# battery_monitor.net
KiCad netlist of a schematic drawn in Altium Designer
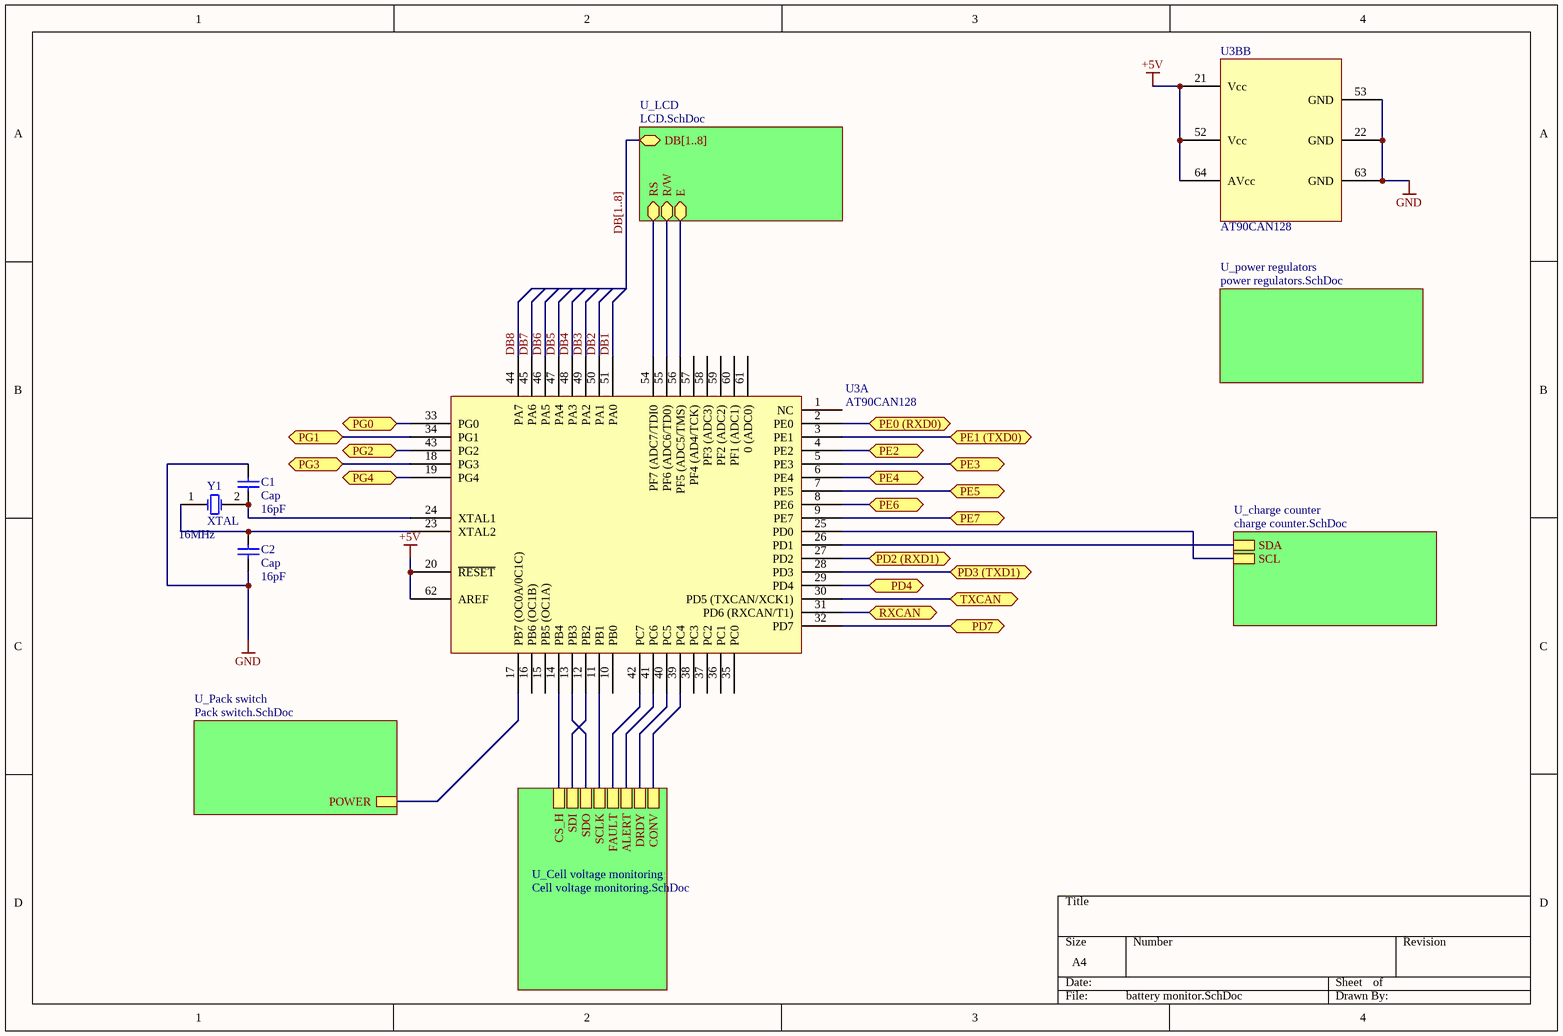
[diagram p0: battery monitor.SchDoc]

(export (version "E")
  (design (tool "Eeschema 10.0.6"))
  (components
    (comp (ref "C1")
      (value "Cap")
      (footprint "C0805")
      (description "Capacitor")
      (fields (field (name "ALTIUM_VALUE") "16pF") (field (name "PUBLISHER") "Altium Limited"))
      (libsource (lib "Miscellaneous Devices") (part "Cap"))
    )
    (comp (ref "C2")
      (value "Cap")
      (footprint "C0805")
      (description "Capacitor")
      (fields (field (name "ALTIUM_VALUE") "16pF") (field (name "PUBLISHER") "Altium Limited"))
      (libsource (lib "Miscellaneous Devices") (part "Cap"))
    )
    (comp (ref "U3")
      (value "AT90CAN128")
      (footprint "TQFP80P1600X1600X120-64N")
      (libsource (lib "") (part "AT90CAN128_1"))
    )
    (comp (ref "U3B")
      (value "AT90CAN128")
      (footprint "TQFP80P1600X1600X120-64N")
      (libsource (lib "AT90CAN128") (part "AT90CAN128"))
    )
    (comp (ref "Y1")
      (value "XTAL")
      (footprint "R38")
      (description "Crystal Oscillator")
      (fields (field (name "ALTIUM_VALUE") "16MHz") (field (name "PUBLISHER") "Altium Limited"))
      (libsource (lib "Miscellaneous Devices") (part "XTAL"))
    )
  )
  (nets
    (net (code "1") (name "+5V") (class "Default")
      (node (ref "U3") (pin "20") (pinfunction "~{RESET}_20") (pintype "passive"))
      (node (ref "U3") (pin "62") (pinfunction "AREF_62") (pintype "passive"))
      (node (ref "U3B") (pin "21") (pinfunction "Vcc_21") (pintype "passive"))
      (node (ref "U3B") (pin "52") (pinfunction "Vcc_52") (pintype "passive"))
      (node (ref "U3B") (pin "64") (pinfunction "AVcc_64") (pintype "passive"))
    )
    (net (code "2") (name "/ALERT") (class "Default")
      (node (ref "U3") (pin "41") (pinfunction "PC6_41") (pintype "passive"))
    )
    (net (code "3") (name "/CONV") (class "Default")
      (node (ref "U3") (pin "39") (pinfunction "PC4_39") (pintype "passive"))
    )
    (net (code "4") (name "/CS_H") (class "Default")
      (node (ref "U3") (pin "14") (pinfunction "PB4_14") (pintype "passive"))
    )
    (net (code "5") (name "/DB1") (class "Default")
      (node (ref "U3") (pin "51") (pinfunction "PA0_51") (pintype "passive"))
    )
    (net (code "6") (name "/DB2") (class "Default")
      (node (ref "U3") (pin "50") (pinfunction "PA1_50") (pintype "passive"))
    )
    (net (code "7") (name "/DB3") (class "Default")
      (node (ref "U3") (pin "49") (pinfunction "PA2_49") (pintype "passive"))
    )
    (net (code "8") (name "/DB4") (class "Default")
      (node (ref "U3") (pin "48") (pinfunction "PA3_48") (pintype "passive"))
    )
    (net (code "9") (name "/DB5") (class "Default")
      (node (ref "U3") (pin "47") (pinfunction "PA4_47") (pintype "passive"))
    )
    (net (code "10") (name "/DB6") (class "Default")
      (node (ref "U3") (pin "46") (pinfunction "PA5_46") (pintype "passive"))
    )
    (net (code "11") (name "/DB7") (class "Default")
      (node (ref "U3") (pin "45") (pinfunction "PA6_45") (pintype "passive"))
    )
    (net (code "12") (name "/DB8") (class "Default")
      (node (ref "U3") (pin "44") (pinfunction "PA7_44") (pintype "passive"))
    )
    (net (code "14") (name "/DRDY") (class "Default")
      (node (ref "U3") (pin "40") (pinfunction "PC5_40") (pintype "passive"))
    )
    (net (code "15") (name "/E") (class "Default")
      (node (ref "U3") (pin "56") (pinfunction "PF5_(ADC5/TMS)_56") (pintype "passive"))
    )
    (net (code "16") (name "/FAULT") (class "Default")
      (node (ref "U3") (pin "42") (pinfunction "PC7_42") (pintype "passive"))
    )
    (net (code "17") (name "/PD2 (RXD1)") (class "Default")
      (node (ref "U3") (pin "27") (pinfunction "PD2_27") (pintype "passive"))
    )
    (net (code "18") (name "/PD3 (TXD1)") (class "Default")
      (node (ref "U3") (pin "28") (pinfunction "PD3_28") (pintype "passive"))
    )
    (net (code "19") (name "/PD4") (class "Default")
      (node (ref "U3") (pin "29") (pinfunction "PD4_29") (pintype "passive"))
    )
    (net (code "20") (name "/PD7") (class "Default")
      (node (ref "U3") (pin "32") (pinfunction "PD7_32") (pintype "passive"))
    )
    (net (code "21") (name "/PE0 (RXD0)") (class "Default")
      (node (ref "U3") (pin "2") (pinfunction "PE0_2") (pintype "passive"))
    )
    (net (code "22") (name "/PE1 (TXD0)") (class "Default")
      (node (ref "U3") (pin "3") (pinfunction "PE1_3") (pintype "passive"))
    )
    (net (code "23") (name "/PE2") (class "Default")
      (node (ref "U3") (pin "4") (pinfunction "PE2_4") (pintype "passive"))
    )
    (net (code "24") (name "/PE3") (class "Default")
      (node (ref "U3") (pin "5") (pinfunction "PE3_5") (pintype "passive"))
    )
    (net (code "25") (name "/PE4") (class "Default")
      (node (ref "U3") (pin "6") (pinfunction "PE4_6") (pintype "passive"))
    )
    (net (code "26") (name "/PE5") (class "Default")
      (node (ref "U3") (pin "7") (pinfunction "PE5_7") (pintype "passive"))
    )
    (net (code "27") (name "/PE6") (class "Default")
      (node (ref "U3") (pin "8") (pinfunction "PE6_8") (pintype "passive"))
    )
    (net (code "28") (name "/PE7") (class "Default")
      (node (ref "U3") (pin "9") (pinfunction "PE7_9") (pintype "passive"))
    )
    (net (code "29") (name "/PG0") (class "Default")
      (node (ref "U3") (pin "33") (pinfunction "PG0_33") (pintype "passive"))
    )
    (net (code "30") (name "/PG1") (class "Default")
      (node (ref "U3") (pin "34") (pinfunction "PG1_34") (pintype "passive"))
    )
    (net (code "31") (name "/PG2") (class "Default")
      (node (ref "U3") (pin "43") (pinfunction "PG2_43") (pintype "passive"))
    )
    (net (code "32") (name "/PG3") (class "Default")
      (node (ref "U3") (pin "18") (pinfunction "PG3_18") (pintype "passive"))
    )
    (net (code "33") (name "/PG4") (class "Default")
      (node (ref "U3") (pin "19") (pinfunction "PG4_19") (pintype "passive"))
    )
    (net (code "34") (name "/POWER") (class "Default")
      (node (ref "U3") (pin "17") (pinfunction "PB7_(OC0A/0C1C)_17") (pintype "passive"))
    )
    (net (code "35") (name "/RS") (class "Default")
      (node (ref "U3") (pin "54") (pinfunction "PF7_(ADC7/TDI0_54") (pintype "passive"))
    )
    (net (code "36") (name "/RXCAN") (class "Default")
      (node (ref "U3") (pin "31") (pinfunction "PD6_(RXCAN/T1)_31") (pintype "passive"))
    )
    (net (code "37") (name "/R{slash}W") (class "Default")
      (node (ref "U3") (pin "55") (pinfunction "PF6_(ADC6/TD0)_55") (pintype "passive"))
    )
    (net (code "38") (name "/SCL") (class "Default")
      (node (ref "U3") (pin "25") (pinfunction "PD0_25") (pintype "passive"))
    )
    (net (code "39") (name "/SCLK") (class "Default")
      (node (ref "U3") (pin "11") (pinfunction "PB1_11") (pintype "passive"))
    )
    (net (code "40") (name "/SDA") (class "Default")
      (node (ref "U3") (pin "26") (pinfunction "PD1_26") (pintype "passive"))
    )
    (net (code "41") (name "/SDI") (class "Default")
      (node (ref "U3") (pin "12") (pinfunction "PB2_12") (pintype "passive"))
    )
    (net (code "42") (name "/SDO") (class "Default")
      (node (ref "U3") (pin "13") (pinfunction "PB3_13") (pintype "passive"))
    )
    (net (code "43") (name "/TXCAN") (class "Default")
      (node (ref "U3") (pin "30") (pinfunction "PD5_(TXCAN/XCK1)_30") (pintype "passive"))
    )
    (net (code "44") (name "GND") (class "Default")
      (node (ref "C1") (pin "2") (pinfunction "2_2") (pintype "passive"))
      (node (ref "C2") (pin "2") (pinfunction "2_2") (pintype "passive"))
      (node (ref "U3B") (pin "22") (pinfunction "GND_22") (pintype "passive"))
      (node (ref "U3B") (pin "53") (pinfunction "GND_53") (pintype "passive"))
      (node (ref "U3B") (pin "63") (pinfunction "GND_63") (pintype "passive"))
    )
    (net (code "45") (name "Net-(U3A-XTAL1)") (class "Default")
      (node (ref "C1") (pin "1") (pinfunction "1_1") (pintype "passive"))
      (node (ref "U3") (pin "24") (pinfunction "XTAL1_24") (pintype "passive"))
      (node (ref "Y1") (pin "2") (pinfunction "OSC2_2") (pintype "passive"))
    )
    (net (code "46") (name "Net-(U3A-XTAL2)") (class "Default")
      (node (ref "C2") (pin "1") (pinfunction "1_1") (pintype "passive"))
      (node (ref "U3") (pin "23") (pinfunction "XTAL2_23") (pintype "passive"))
      (node (ref "Y1") (pin "1") (pinfunction "OSC1_1") (pintype "passive"))
    )
    (net (code "47") (name "unconnected-(U3A-0_(ADC0)-Pad61)") (class "Default")
      (node (ref "U3") (pin "61") (pinfunction "0_(ADC0)_61") (pintype "passive"))
    )
    (net (code "48") (name "unconnected-(U3A-NC-Pad1)") (class "Default")
      (node (ref "U3") (pin "1") (pinfunction "NC_1") (pintype "passive"))
    )
    (net (code "49") (name "unconnected-(U3A-PB0-Pad10)") (class "Default")
      (node (ref "U3") (pin "10") (pinfunction "PB0_10") (pintype "passive"))
    )
    (net (code "50") (name "unconnected-(U3A-PB5_(OC1A)-Pad15)") (class "Default")
      (node (ref "U3") (pin "15") (pinfunction "PB5_(OC1A)_15") (pintype "passive"))
    )
    (net (code "51") (name "unconnected-(U3A-PB6_(OC1B)-Pad16)") (class "Default")
      (node (ref "U3") (pin "16") (pinfunction "PB6_(OC1B)_16") (pintype "passive"))
    )
    (net (code "52") (name "unconnected-(U3A-PC0-Pad35)") (class "Default")
      (node (ref "U3") (pin "35") (pinfunction "PC0_35") (pintype "passive"))
    )
    (net (code "53") (name "unconnected-(U3A-PC1-Pad36)") (class "Default")
      (node (ref "U3") (pin "36") (pinfunction "PC1_36") (pintype "passive"))
    )
    (net (code "54") (name "unconnected-(U3A-PC2-Pad37)") (class "Default")
      (node (ref "U3") (pin "37") (pinfunction "PC2_37") (pintype "passive"))
    )
    (net (code "55") (name "unconnected-(U3A-PC3-Pad38)") (class "Default")
      (node (ref "U3") (pin "38") (pinfunction "PC3_38") (pintype "passive"))
    )
    (net (code "56") (name "unconnected-(U3A-PF1_(ADC1)-Pad60)") (class "Default")
      (node (ref "U3") (pin "60") (pinfunction "PF1_(ADC1)_60") (pintype "passive"))
    )
    (net (code "57") (name "unconnected-(U3A-PF2_(ADC2)-Pad59)") (class "Default")
      (node (ref "U3") (pin "59") (pinfunction "PF2_(ADC2)_59") (pintype "passive"))
    )
    (net (code "58") (name "unconnected-(U3A-PF3_(ADC3)-Pad58)") (class "Default")
      (node (ref "U3") (pin "58") (pinfunction "PF3_(ADC3)_58") (pintype "passive"))
    )
    (net (code "59") (name "unconnected-(U3A-PF4_(AD4{slash}TCK)-Pad57)") (class "Default")
      (node (ref "U3") (pin "57") (pinfunction "PF4_(AD4/TCK)_57") (pintype "passive"))
    )
  )
)
